# apple_all.net
KiCad netlist of a schematic drawn in EAGLE
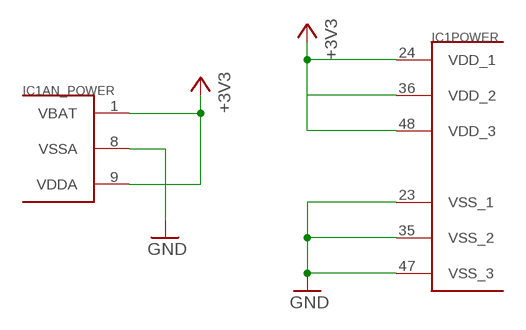
[diagram p0: schematic, sheet 1, part 1 of 2]
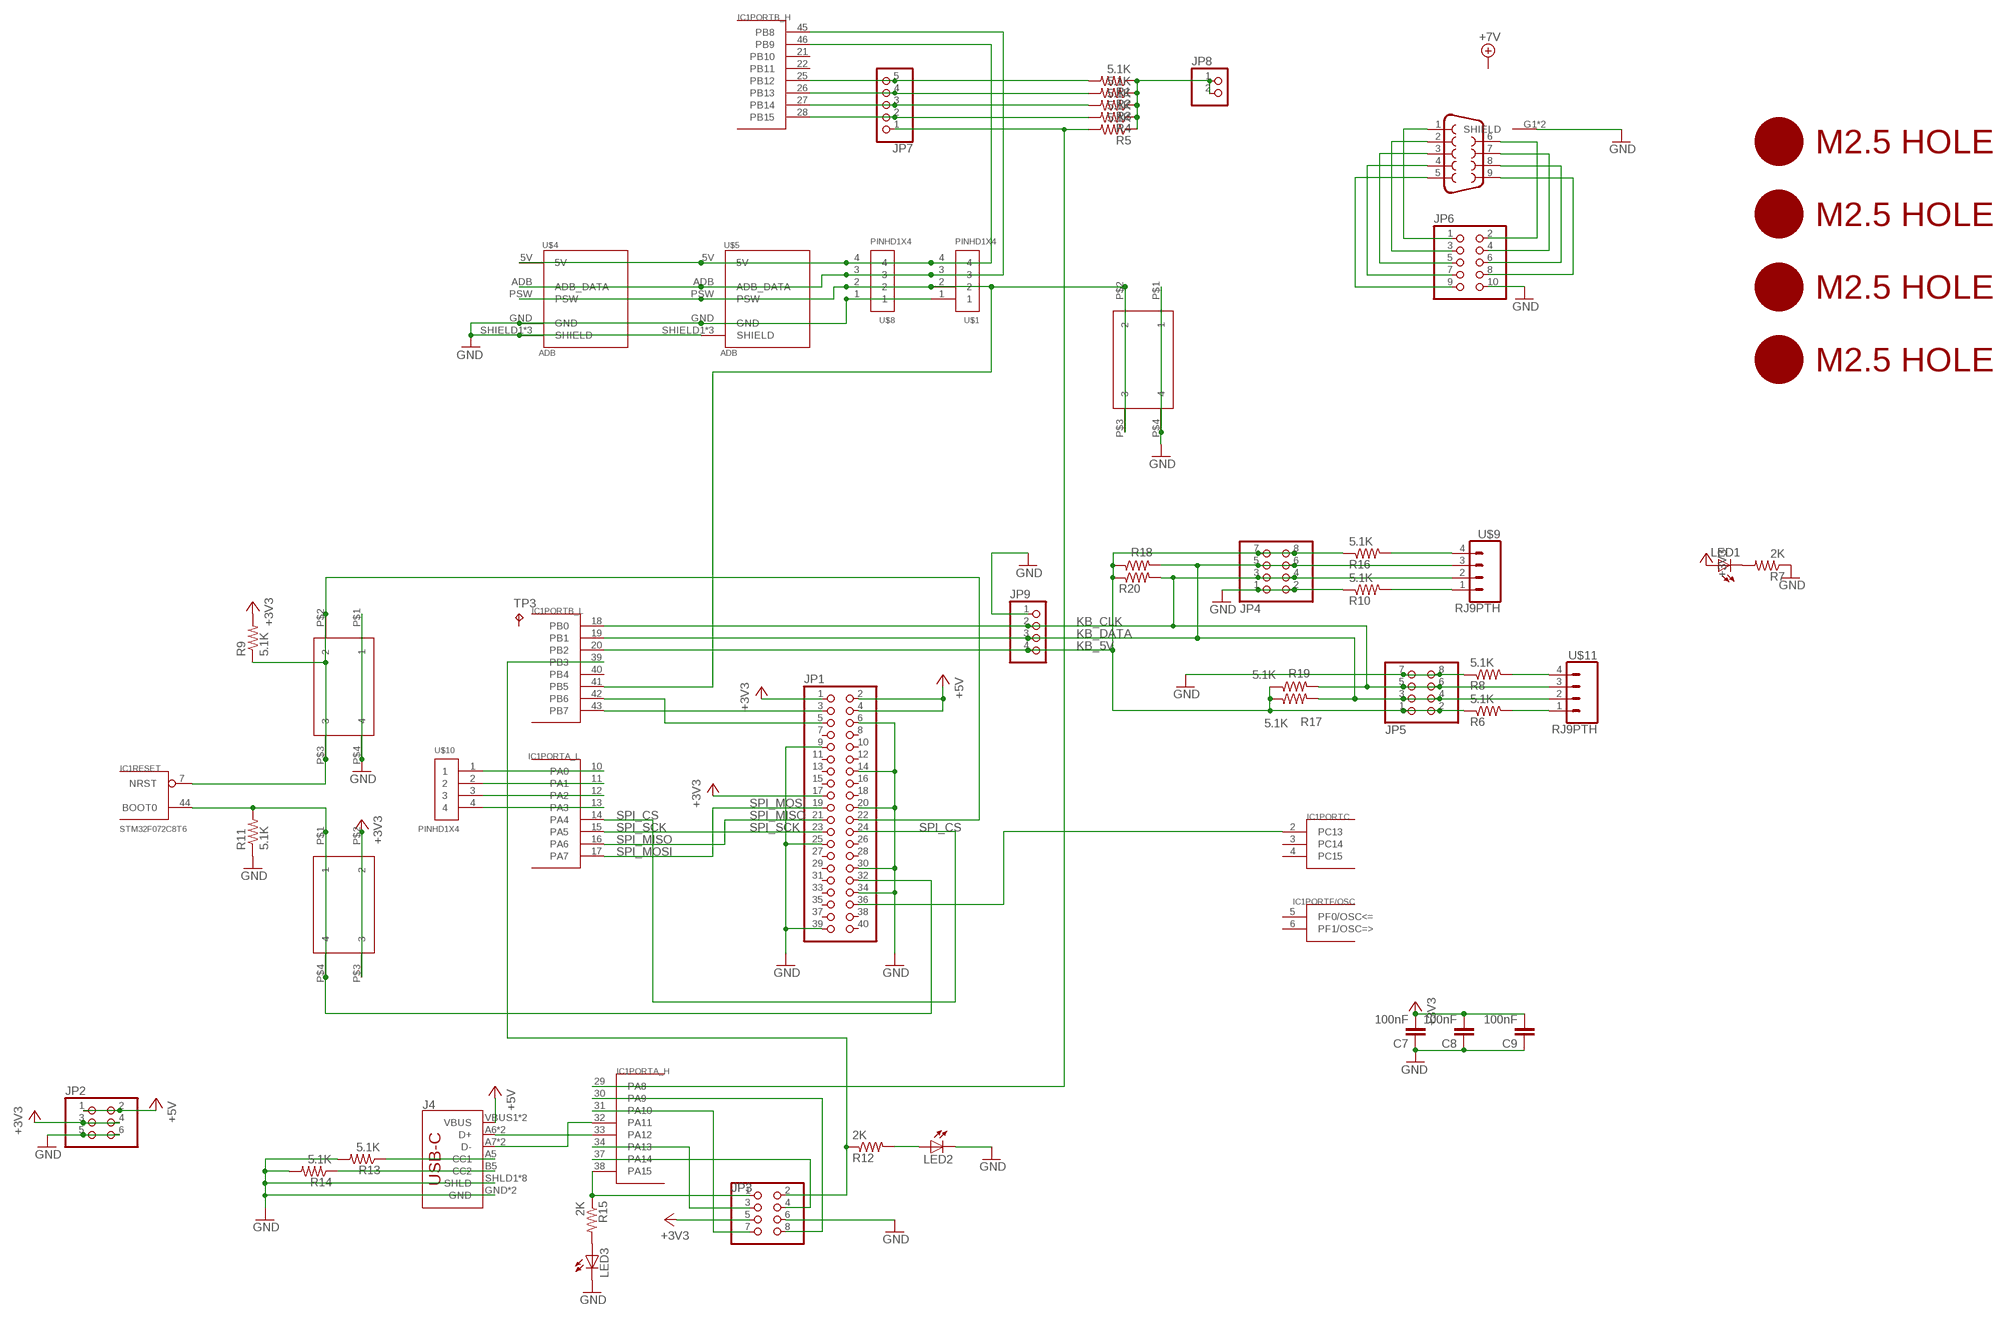
[diagram p1: schematic, sheet 1, part 2 of 2]

(export (version "E")
  (design (tool "Eeschema 10.0.6"))
  (components
    (comp (ref "C7")
      (value "100nF")
      (footprint "eagle-import:0805@1")
      (libsource (lib "eagle-import") (part "CAP0805"))
    )
    (comp (ref "C8")
      (value "100nF")
      (footprint "eagle-import:0805@1")
      (libsource (lib "eagle-import") (part "CAP0805"))
    )
    (comp (ref "C9")
      (value "100nF")
      (footprint "eagle-import:0805@1")
      (libsource (lib "eagle-import") (part "CAP0805"))
    )
    (comp (ref "IC1")
      (value "STM32F072C8T6")
      (footprint "eagle-import:TQFP48")
      (libsource (lib "eagle-import") (part "STM32F072C8T6"))
    )
    (comp (ref "J2")
      (value "DB9FEMALE")
      (footprint "eagle-import:DB9")
      (libsource (lib "eagle-import") (part "DB9FEMALE"))
    )
    (comp (ref "J4")
      (value "USB_C16PIN")
      (footprint "eagle-import:USB-C-16P")
      (libsource (lib "eagle-import") (part "USB_C16PIN"))
    )
    (comp (ref "JP1")
      (value "PINHD-2X20-BIG")
      (footprint "eagle-import:2X20-BIG")
      (libsource (lib "eagle-import") (part "PINHD-2X20-BIG"))
    )
    (comp (ref "JP2")
      (value "PINHD-2X3")
      (footprint "eagle-import:2X03")
      (libsource (lib "eagle-import") (part "PINHD-2X3"))
    )
    (comp (ref "JP3")
      (value "PINHD-2X4")
      (footprint "eagle-import:2X04")
      (libsource (lib "eagle-import") (part "PINHD-2X4"))
    )
    (comp (ref "JP4")
      (value "PINHD-2X4")
      (footprint "eagle-import:2X04")
      (libsource (lib "eagle-import") (part "PINHD-2X4"))
    )
    (comp (ref "JP5")
      (value "PINHD-2X4")
      (footprint "eagle-import:2X04")
      (libsource (lib "eagle-import") (part "PINHD-2X4"))
    )
    (comp (ref "JP6")
      (value "PINHD-2X5")
      (footprint "eagle-import:2X05")
      (libsource (lib "eagle-import") (part "PINHD-2X5"))
    )
    (comp (ref "JP7")
      (value "PINHD-1X5")
      (footprint "eagle-import:1X05")
      (libsource (lib "eagle-import") (part "PINHD-1X5"))
    )
    (comp (ref "JP8")
      (value "PINHD-1X2")
      (footprint "eagle-import:1X02")
      (libsource (lib "eagle-import") (part "PINHD-1X2"))
    )
    (comp (ref "JP9")
      (value "PINHD-1X4")
      (footprint "eagle-import:1X04")
      (libsource (lib "eagle-import") (part "PINHD-1X4"))
    )
    (comp (ref "LED1")
      (value "LEDCHIP-LED0805")
      (footprint "eagle-import:CHIP-LED0805")
      (libsource (lib "eagle-import") (part "LEDCHIP-LED0805"))
    )
    (comp (ref "LED2")
      (value "LEDCHIP-LED0805")
      (footprint "eagle-import:CHIP-LED0805")
      (libsource (lib "eagle-import") (part "LEDCHIP-LED0805"))
    )
    (comp (ref "LED3")
      (value "LEDCHIP-LED0805")
      (footprint "eagle-import:CHIP-LED0805")
      (libsource (lib "eagle-import") (part "LEDCHIP-LED0805"))
    )
    (comp (ref "R1")
      (value "5.1K")
      (footprint "eagle-import:0805")
      (libsource (lib "eagle-import") (part "RESISTOR0805-RES"))
    )
    (comp (ref "R2")
      (value "5.1K")
      (footprint "eagle-import:0805")
      (libsource (lib "eagle-import") (part "RESISTOR0805-RES"))
    )
    (comp (ref "R3")
      (value "5.1K")
      (footprint "eagle-import:0805")
      (libsource (lib "eagle-import") (part "RESISTOR0805-RES"))
    )
    (comp (ref "R4")
      (value "5.1K")
      (footprint "eagle-import:0805")
      (libsource (lib "eagle-import") (part "RESISTOR0805-RES"))
    )
    (comp (ref "R5")
      (value "5.1K")
      (footprint "eagle-import:0805")
      (libsource (lib "eagle-import") (part "RESISTOR0805-RES"))
    )
    (comp (ref "R6")
      (value "5.1K")
      (footprint "eagle-import:0805")
      (libsource (lib "eagle-import") (part "RESISTOR0805-RES"))
    )
    (comp (ref "R7")
      (value "2K")
      (footprint "eagle-import:0805")
      (libsource (lib "eagle-import") (part "RESISTOR0805-RES"))
    )
    (comp (ref "R8")
      (value "5.1K")
      (footprint "eagle-import:0805")
      (libsource (lib "eagle-import") (part "RESISTOR0805-RES"))
    )
    (comp (ref "R9")
      (value "5.1K")
      (footprint "eagle-import:0805")
      (libsource (lib "eagle-import") (part "RESISTOR0805-RES"))
    )
    (comp (ref "R10")
      (value "5.1K")
      (footprint "eagle-import:0805")
      (libsource (lib "eagle-import") (part "RESISTOR0805-RES"))
    )
    (comp (ref "R11")
      (value "5.1K")
      (footprint "eagle-import:0805")
      (libsource (lib "eagle-import") (part "RESISTOR0805-RES"))
    )
    (comp (ref "R12")
      (value "2K")
      (footprint "eagle-import:0805")
      (libsource (lib "eagle-import") (part "RESISTOR0805-RES"))
    )
    (comp (ref "R13")
      (value "5.1K")
      (footprint "eagle-import:0805")
      (libsource (lib "eagle-import") (part "RESISTOR0805-RES"))
    )
    (comp (ref "R14")
      (value "5.1K")
      (footprint "eagle-import:0805")
      (libsource (lib "eagle-import") (part "RESISTOR0805-RES"))
    )
    (comp (ref "R15")
      (value "2K")
      (footprint "eagle-import:0805")
      (libsource (lib "eagle-import") (part "RESISTOR0805-RES"))
    )
    (comp (ref "R16")
      (value "5.1K")
      (footprint "eagle-import:0805")
      (libsource (lib "eagle-import") (part "RESISTOR0805-RES"))
    )
    (comp (ref "R17")
      (value "5.1K")
      (footprint "eagle-import:0805")
      (libsource (lib "eagle-import") (part "RESISTOR0805-RES"))
    )
    (comp (ref "R18")
      (value "5.1K")
      (footprint "eagle-import:0805")
      (libsource (lib "eagle-import") (part "RESISTOR0805-RES"))
    )
    (comp (ref "R19")
      (value "5.1K")
      (footprint "eagle-import:0805")
      (libsource (lib "eagle-import") (part "RESISTOR0805-RES"))
    )
    (comp (ref "R20")
      (value "5.1K")
      (footprint "eagle-import:0805")
      (libsource (lib "eagle-import") (part "RESISTOR0805-RES"))
    )
    (comp (ref "SW1")
      (value "324_SW")
      (footprint "eagle-import:342_SWICH_FOOT")
      (libsource (lib "eagle-import") (part "324_SW"))
    )
    (comp (ref "SW2")
      (value "324_SW")
      (footprint "eagle-import:342_SWICH_FOOT")
      (libsource (lib "eagle-import") (part "324_SW"))
    )
    (comp (ref "SW3")
      (value "324_SW")
      (footprint "eagle-import:342_SWICH_FOOT")
      (libsource (lib "eagle-import") (part "324_SW"))
    )
    (comp (ref "TP3")
      (value "TPTP12R")
      (footprint "eagle-import:TP12R")
      (libsource (lib "eagle-import") (part "TPTP12R"))
    )
    (comp (ref "U$1")
      (value "PINHD1X4")
      (footprint "eagle-import:1X04-CLEANBIG")
      (libsource (lib "eagle-import") (part "PINHD1X4"))
    )
    (comp (ref "U$2")
      (value "M2.5HOLE")
      (footprint "eagle-import:M2.5HOLE")
      (libsource (lib "eagle-import") (part "M2.5HOLE"))
    )
    (comp (ref "U$3")
      (value "M2.5HOLE")
      (footprint "eagle-import:M2.5HOLE")
      (libsource (lib "eagle-import") (part "M2.5HOLE"))
    )
    (comp (ref "U$4")
      (value "ADB")
      (footprint "eagle-import:DIN4")
      (libsource (lib "eagle-import") (part "ADB"))
    )
    (comp (ref "U$5")
      (value "ADB")
      (footprint "eagle-import:DIN4")
      (libsource (lib "eagle-import") (part "ADB"))
    )
    (comp (ref "U$6")
      (value "M2.5HOLE")
      (footprint "eagle-import:M2.5HOLE")
      (libsource (lib "eagle-import") (part "M2.5HOLE"))
    )
    (comp (ref "U$7")
      (value "M2.5HOLE")
      (footprint "eagle-import:M2.5HOLE")
      (libsource (lib "eagle-import") (part "M2.5HOLE"))
    )
    (comp (ref "U$8")
      (value "PINHD1X4")
      (footprint "eagle-import:1X04-CLEANBIG")
      (libsource (lib "eagle-import") (part "PINHD1X4"))
    )
    (comp (ref "U$9")
      (value "RJ9PTH")
      (footprint "eagle-import:RJ9")
      (libsource (lib "eagle-import") (part "RJ9PTH"))
    )
    (comp (ref "U$10")
      (value "PINHD1X4")
      (footprint "eagle-import:1X04-CLEANBIG")
      (libsource (lib "eagle-import") (part "PINHD1X4"))
    )
    (comp (ref "U$11")
      (value "RJ9PTH")
      (footprint "eagle-import:RJ9")
      (libsource (lib "eagle-import") (part "RJ9PTH"))
    )
  )
  (nets
    (net (code "1") (name "+3V3") (class "Default")
      (node (ref "C7") (pin "2") (pinfunction "2_2") (pintype "passive"))
      (node (ref "C8") (pin "2") (pinfunction "2_2") (pintype "passive"))
      (node (ref "C9") (pin "2") (pinfunction "2_2") (pintype "passive"))
      (node (ref "IC1") (pin "1") (pinfunction "VBAT_1") (pintype "power_in"))
      (node (ref "IC1") (pin "24") (pinfunction "VDD_1_24") (pintype "power_in"))
      (node (ref "IC1") (pin "36") (pinfunction "VDD_2_36") (pintype "power_in"))
      (node (ref "IC1") (pin "48") (pinfunction "VDD_3_48") (pintype "power_in"))
      (node (ref "IC1") (pin "9") (pinfunction "VDDA_9") (pintype "power_in"))
      (node (ref "JP1") (pin "1") (pinfunction "1_1") (pintype "passive"))
      (node (ref "JP1") (pin "17") (pinfunction "17_17") (pintype "passive"))
      (node (ref "JP2") (pin "3") (pinfunction "3_3") (pintype "passive"))
      (node (ref "JP2") (pin "4") (pinfunction "4_4") (pintype "passive"))
      (node (ref "JP3") (pin "5") (pinfunction "5_5") (pintype "passive"))
      (node (ref "LED1") (pin "A") (pinfunction "A_A") (pintype "passive"))
      (node (ref "R9") (pin "2") (pinfunction "2_2") (pintype "passive"))
      (node (ref "SW2") (pin "P$2") (pinfunction "2_P$2") (pintype "bidirectional"))
      (node (ref "SW2") (pin "P$3") (pinfunction "3_P$3") (pintype "bidirectional"))
    )
    (net (code "2") (name "+5V") (class "Default")
      (node (ref "J4") (pin "VBUS1") (pinfunction "VBUS_VBUS1") (pintype "bidirectional"))
      (node (ref "J4") (pin "VBUS2") (pinfunction "VBUS_VBUS2") (pintype "bidirectional"))
      (node (ref "JP1") (pin "2") (pinfunction "2_2") (pintype "passive"))
      (node (ref "JP1") (pin "4") (pinfunction "4_4") (pintype "passive"))
      (node (ref "JP2") (pin "1") (pinfunction "1_1") (pintype "passive"))
      (node (ref "JP2") (pin "2") (pinfunction "2_2") (pintype "passive"))
    )
    (net (code "4") (name "/KB_5V") (class "Default")
      (node (ref "IC1") (pin "20") (pinfunction "PB2_20") (pintype "bidirectional"))
      (node (ref "JP4") (pin "7") (pinfunction "7_7") (pintype "passive"))
      (node (ref "JP4") (pin "8") (pinfunction "8_8") (pintype "passive"))
      (node (ref "JP5") (pin "1") (pinfunction "1_1") (pintype "passive"))
      (node (ref "JP5") (pin "2") (pinfunction "2_2") (pintype "passive"))
      (node (ref "JP9") (pin "4") (pinfunction "4_4") (pintype "passive"))
      (node (ref "R16") (pin "1") (pinfunction "1_1") (pintype "passive"))
      (node (ref "R17") (pin "1") (pinfunction "1_1") (pintype "passive"))
      (node (ref "R18") (pin "1") (pinfunction "1_1") (pintype "passive"))
      (node (ref "R19") (pin "1") (pinfunction "1_1") (pintype "passive"))
      (node (ref "R20") (pin "1") (pinfunction "1_1") (pintype "passive"))
      (node (ref "R6") (pin "1") (pinfunction "1_1") (pintype "passive"))
    )
    (net (code "5") (name "/KB_CLK") (class "Default")
      (node (ref "IC1") (pin "18") (pinfunction "PB0_18") (pintype "bidirectional"))
      (node (ref "JP4") (pin "3") (pinfunction "3_3") (pintype "passive"))
      (node (ref "JP4") (pin "4") (pinfunction "4_4") (pintype "passive"))
      (node (ref "JP5") (pin "5") (pinfunction "5_5") (pintype "passive"))
      (node (ref "JP5") (pin "6") (pinfunction "6_6") (pintype "passive"))
      (node (ref "JP9") (pin "2") (pinfunction "2_2") (pintype "passive"))
      (node (ref "R19") (pin "2") (pinfunction "2_2") (pintype "passive"))
      (node (ref "R20") (pin "2") (pinfunction "2_2") (pintype "passive"))
      (node (ref "U$11") (pin "3") (pinfunction "3_3") (pintype "passive"))
      (node (ref "U$9") (pin "2") (pinfunction "2_2") (pintype "passive"))
    )
    (net (code "6") (name "/KB_DATA") (class "Default")
      (node (ref "IC1") (pin "19") (pinfunction "PB1_19") (pintype "bidirectional"))
      (node (ref "JP4") (pin "5") (pinfunction "5_5") (pintype "passive"))
      (node (ref "JP4") (pin "6") (pinfunction "6_6") (pintype "passive"))
      (node (ref "JP5") (pin "3") (pinfunction "3_3") (pintype "passive"))
      (node (ref "JP5") (pin "4") (pinfunction "4_4") (pintype "passive"))
      (node (ref "JP9") (pin "3") (pinfunction "3_3") (pintype "passive"))
      (node (ref "R17") (pin "2") (pinfunction "2_2") (pintype "passive"))
      (node (ref "R18") (pin "2") (pinfunction "2_2") (pintype "passive"))
      (node (ref "U$11") (pin "2") (pinfunction "2_2") (pintype "passive"))
      (node (ref "U$9") (pin "3") (pinfunction "3_3") (pintype "passive"))
    )
    (net (code "7") (name "/SPI_CS") (class "Default")
      (node (ref "IC1") (pin "14") (pinfunction "PA4_14") (pintype "bidirectional"))
      (node (ref "JP1") (pin "24") (pinfunction "24_24") (pintype "passive"))
    )
    (net (code "8") (name "/SPI_MISO") (class "Default")
      (node (ref "IC1") (pin "16") (pinfunction "PA6_16") (pintype "bidirectional"))
      (node (ref "JP1") (pin "21") (pinfunction "21_21") (pintype "passive"))
    )
    (net (code "9") (name "/SPI_MOSI") (class "Default")
      (node (ref "IC1") (pin "17") (pinfunction "PA7_17") (pintype "bidirectional"))
      (node (ref "JP1") (pin "19") (pinfunction "19_19") (pintype "passive"))
    )
    (net (code "10") (name "/SPI_SCK") (class "Default")
      (node (ref "IC1") (pin "15") (pinfunction "PA5_15") (pintype "bidirectional"))
      (node (ref "JP1") (pin "23") (pinfunction "23_23") (pintype "passive"))
    )
    (net (code "11") (name "GND") (class "Default")
      (node (ref "C7") (pin "1") (pinfunction "1_1") (pintype "passive"))
      (node (ref "C8") (pin "1") (pinfunction "1_1") (pintype "passive"))
      (node (ref "C9") (pin "1") (pinfunction "1_1") (pintype "passive"))
      (node (ref "IC1") (pin "23") (pinfunction "VSS_1_23") (pintype "power_in"))
      (node (ref "IC1") (pin "35") (pinfunction "VSS_2_35") (pintype "power_in"))
      (node (ref "IC1") (pin "47") (pinfunction "VSS_3_47") (pintype "power_in"))
      (node (ref "IC1") (pin "8") (pinfunction "VSSA_8") (pintype "power_in"))
      (node (ref "J2") (pin "G1") (pinfunction "SHIELD_G1") (pintype "bidirectional"))
      (node (ref "J2") (pin "G2") (pinfunction "SHIELD_G2") (pintype "bidirectional"))
      (node (ref "J4") (pin "GND") (pinfunction "GND_GND") (pintype "bidirectional"))
      (node (ref "J4") (pin "GND2") (pinfunction "GND_GND2") (pintype "bidirectional"))
      (node (ref "J4") (pin "SHLD1") (pinfunction "SHLD_SHLD1") (pintype "bidirectional"))
      (node (ref "J4") (pin "SHLD2") (pinfunction "SHLD_SHLD2") (pintype "bidirectional"))
      (node (ref "J4") (pin "SHLD3") (pinfunction "SHLD_SHLD3") (pintype "bidirectional"))
      (node (ref "J4") (pin "SHLD4") (pinfunction "SHLD_SHLD4") (pintype "bidirectional"))
      (node (ref "J4") (pin "SHLD5") (pinfunction "SHLD_SHLD5") (pintype "bidirectional"))
      (node (ref "J4") (pin "SHLD6") (pinfunction "SHLD_SHLD6") (pintype "bidirectional"))
      (node (ref "J4") (pin "SHLD7") (pinfunction "SHLD_SHLD7") (pintype "bidirectional"))
      (node (ref "J4") (pin "SHLD8") (pinfunction "SHLD_SHLD8") (pintype "bidirectional"))
      (node (ref "JP1") (pin "14") (pinfunction "14_14") (pintype "passive"))
      (node (ref "JP1") (pin "20") (pinfunction "20_20") (pintype "passive"))
      (node (ref "JP1") (pin "25") (pinfunction "25_25") (pintype "passive"))
      (node (ref "JP1") (pin "30") (pinfunction "30_30") (pintype "passive"))
      (node (ref "JP1") (pin "34") (pinfunction "34_34") (pintype "passive"))
      (node (ref "JP1") (pin "39") (pinfunction "39_39") (pintype "passive"))
      (node (ref "JP1") (pin "6") (pinfunction "6_6") (pintype "passive"))
      (node (ref "JP1") (pin "9") (pinfunction "9_9") (pintype "passive"))
      (node (ref "JP2") (pin "5") (pinfunction "5_5") (pintype "passive"))
      (node (ref "JP2") (pin "6") (pinfunction "6_6") (pintype "passive"))
      (node (ref "JP3") (pin "6") (pinfunction "6_6") (pintype "passive"))
      (node (ref "JP4") (pin "1") (pinfunction "1_1") (pintype "passive"))
      (node (ref "JP4") (pin "2") (pinfunction "2_2") (pintype "passive"))
      (node (ref "JP5") (pin "7") (pinfunction "7_7") (pintype "passive"))
      (node (ref "JP5") (pin "8") (pinfunction "8_8") (pintype "passive"))
      (node (ref "JP6") (pin "10") (pinfunction "10_10") (pintype "passive"))
      (node (ref "JP9") (pin "1") (pinfunction "1_1") (pintype "passive"))
      (node (ref "LED2") (pin "C") (pinfunction "C_C") (pintype "passive"))
      (node (ref "LED3") (pin "C") (pinfunction "C_C") (pintype "passive"))
      (node (ref "R10") (pin "1") (pinfunction "1_1") (pintype "passive"))
      (node (ref "R11") (pin "1") (pinfunction "1_1") (pintype "passive"))
      (node (ref "R13") (pin "2") (pinfunction "2_2") (pintype "passive"))
      (node (ref "R14") (pin "2") (pinfunction "2_2") (pintype "passive"))
      (node (ref "R7") (pin "1") (pinfunction "1_1") (pintype "passive"))
      (node (ref "R8") (pin "1") (pinfunction "1_1") (pintype "passive"))
      (node (ref "SW1") (pin "P$1") (pinfunction "1_P$1") (pintype "bidirectional"))
      (node (ref "SW1") (pin "P$4") (pinfunction "4_P$4") (pintype "bidirectional"))
      (node (ref "SW3") (pin "P$1") (pinfunction "1_P$1") (pintype "bidirectional"))
      (node (ref "SW3") (pin "P$4") (pinfunction "4_P$4") (pintype "bidirectional"))
      (node (ref "U$1") (pin "1") (pinfunction "1_1") (pintype "bidirectional"))
      (node (ref "U$4") (pin "GND") (pinfunction "GND_GND") (pintype "bidirectional"))
      (node (ref "U$4") (pin "SHIELD1") (pinfunction "SHIELD_SHIELD1") (pintype "bidirectional"))
      (node (ref "U$4") (pin "SHIELD2") (pinfunction "SHIELD_SHIELD2") (pintype "bidirectional"))
      (node (ref "U$4") (pin "SHIELD3") (pinfunction "SHIELD_SHIELD3") (pintype "bidirectional"))
      (node (ref "U$5") (pin "GND") (pinfunction "GND_GND") (pintype "bidirectional"))
      (node (ref "U$5") (pin "SHIELD1") (pinfunction "SHIELD_SHIELD1") (pintype "bidirectional"))
      (node (ref "U$5") (pin "SHIELD2") (pinfunction "SHIELD_SHIELD2") (pintype "bidirectional"))
      (node (ref "U$5") (pin "SHIELD3") (pinfunction "SHIELD_SHIELD3") (pintype "bidirectional"))
      (node (ref "U$8") (pin "1") (pinfunction "1_1") (pintype "bidirectional"))
    )
    (net (code "12") (name "Net-(IC1B-PA8)") (class "Default")
      (node (ref "IC1") (pin "29") (pinfunction "PA8_29") (pintype "bidirectional"))
      (node (ref "JP7") (pin "1") (pinfunction "1_1") (pintype "passive"))
      (node (ref "R5") (pin "2") (pinfunction "2_2") (pintype "passive"))
    )
    (net (code "13") (name "Net-(IC1B-PA9)") (class "Default")
      (node (ref "IC1") (pin "30") (pinfunction "PA9_30") (pintype "bidirectional"))
      (node (ref "JP3") (pin "8") (pinfunction "8_8") (pintype "passive"))
    )
    (net (code "14") (name "Net-(IC1B-PA10)") (class "Default")
      (node (ref "IC1") (pin "31") (pinfunction "PA10_31") (pintype "bidirectional"))
      (node (ref "JP3") (pin "7") (pinfunction "7_7") (pintype "passive"))
    )
    (net (code "15") (name "Net-(IC1B-PA11)") (class "Default")
      (node (ref "IC1") (pin "32") (pinfunction "PA11_32") (pintype "bidirectional"))
      (node (ref "J4") (pin "A7") (pinfunction "D-_A7") (pintype "bidirectional"))
      (node (ref "J4") (pin "B7") (pinfunction "D-_B7") (pintype "bidirectional"))
    )
    (net (code "16") (name "Net-(IC1B-PA12)") (class "Default")
      (node (ref "IC1") (pin "33") (pinfunction "PA12_33") (pintype "bidirectional"))
      (node (ref "J4") (pin "A6") (pinfunction "D+_A6") (pintype "bidirectional"))
      (node (ref "J4") (pin "B6") (pinfunction "D+_B6") (pintype "bidirectional"))
    )
    (net (code "17") (name "Net-(IC1B-PA13)") (class "Default")
      (node (ref "IC1") (pin "34") (pinfunction "PA13_34") (pintype "bidirectional"))
      (node (ref "JP3") (pin "3") (pinfunction "3_3") (pintype "passive"))
    )
    (net (code "18") (name "Net-(IC1B-PA14)") (class "Default")
      (node (ref "IC1") (pin "37") (pinfunction "PA14_37") (pintype "bidirectional"))
      (node (ref "JP3") (pin "4") (pinfunction "4_4") (pintype "passive"))
    )
    (net (code "19") (name "Net-(IC1B-PA15)") (class "Default")
      (node (ref "IC1") (pin "38") (pinfunction "PA15_38") (pintype "bidirectional"))
      (node (ref "JP3") (pin "1") (pinfunction "1_1") (pintype "passive"))
      (node (ref "R15") (pin "1") (pinfunction "1_1") (pintype "passive"))
    )
    (net (code "20") (name "Net-(IC1C-PA0)") (class "Default")
      (node (ref "IC1") (pin "10") (pinfunction "PA0_10") (pintype "bidirectional"))
      (node (ref "U$10") (pin "1") (pinfunction "1_1") (pintype "bidirectional"))
    )
    (net (code "21") (name "Net-(IC1C-PA1)") (class "Default")
      (node (ref "IC1") (pin "11") (pinfunction "PA1_11") (pintype "bidirectional"))
      (node (ref "U$10") (pin "2") (pinfunction "2_2") (pintype "bidirectional"))
    )
    (net (code "22") (name "Net-(IC1C-PA2)") (class "Default")
      (node (ref "IC1") (pin "12") (pinfunction "PA2_12") (pintype "bidirectional"))
      (node (ref "U$10") (pin "3") (pinfunction "3_3") (pintype "bidirectional"))
    )
    (net (code "23") (name "Net-(IC1C-PA3)") (class "Default")
      (node (ref "IC1") (pin "13") (pinfunction "PA3_13") (pintype "bidirectional"))
      (node (ref "U$10") (pin "4") (pinfunction "4_4") (pintype "bidirectional"))
    )
    (net (code "24") (name "Net-(IC1D-PB8)") (class "Default")
      (node (ref "IC1") (pin "45") (pinfunction "PB8_45") (pintype "bidirectional"))
      (node (ref "U$1") (pin "3") (pinfunction "3_3") (pintype "bidirectional"))
      (node (ref "U$4") (pin "ADB") (pinfunction "ADB_DATA_ADB") (pintype "bidirectional"))
      (node (ref "U$5") (pin "ADB") (pinfunction "ADB_DATA_ADB") (pintype "bidirectional"))
      (node (ref "U$8") (pin "3") (pinfunction "3_3") (pintype "bidirectional"))
    )
    (net (code "25") (name "Net-(IC1D-PB9)") (class "Default")
      (node (ref "IC1") (pin "46") (pinfunction "PB9_46") (pintype "bidirectional"))
      (node (ref "U$1") (pin "4") (pinfunction "4_4") (pintype "bidirectional"))
      (node (ref "U$4") (pin "5V") (pinfunction "5V_5V") (pintype "bidirectional"))
      (node (ref "U$5") (pin "5V") (pinfunction "5V_5V") (pintype "bidirectional"))
      (node (ref "U$8") (pin "4") (pinfunction "4_4") (pintype "bidirectional"))
    )
    (net (code "26") (name "Net-(IC1D-PB12)") (class "Default")
      (node (ref "IC1") (pin "25") (pinfunction "PB12_25") (pintype "bidirectional"))
      (node (ref "JP7") (pin "5") (pinfunction "5_5") (pintype "passive"))
      (node (ref "R1") (pin "2") (pinfunction "2_2") (pintype "passive"))
    )
    (net (code "27") (name "Net-(IC1D-PB13)") (class "Default")
      (node (ref "IC1") (pin "26") (pinfunction "PB13_26") (pintype "bidirectional"))
      (node (ref "JP7") (pin "4") (pinfunction "4_4") (pintype "passive"))
      (node (ref "R2") (pin "2") (pinfunction "2_2") (pintype "passive"))
    )
    (net (code "28") (name "Net-(IC1D-PB14)") (class "Default")
      (node (ref "IC1") (pin "27") (pinfunction "PB14_27") (pintype "bidirectional"))
      (node (ref "JP7") (pin "3") (pinfunction "3_3") (pintype "passive"))
      (node (ref "R3") (pin "2") (pinfunction "2_2") (pintype "passive"))
    )
    (net (code "29") (name "Net-(IC1D-PB15)") (class "Default")
      (node (ref "IC1") (pin "28") (pinfunction "PB15_28") (pintype "bidirectional"))
      (node (ref "JP7") (pin "2") (pinfunction "2_2") (pintype "passive"))
      (node (ref "R4") (pin "2") (pinfunction "2_2") (pintype "passive"))
    )
    (net (code "30") (name "Net-(IC1E-PB3)") (class "Default")
      (node (ref "IC1") (pin "39") (pinfunction "PB3_39") (pintype "bidirectional"))
      (node (ref "JP3") (pin "2") (pinfunction "2_2") (pintype "passive"))
      (node (ref "R12") (pin "1") (pinfunction "1_1") (pintype "passive"))
    )
    (net (code "31") (name "Net-(IC1E-PB5)") (class "Default")
      (node (ref "IC1") (pin "41") (pinfunction "PB5_41") (pintype "bidirectional"))
      (node (ref "SW3") (pin "P$2") (pinfunction "2_P$2") (pintype "bidirectional"))
      (node (ref "SW3") (pin "P$3") (pinfunction "3_P$3") (pintype "bidirectional"))
      (node (ref "U$1") (pin "2") (pinfunction "2_2") (pintype "bidirectional"))
      (node (ref "U$4") (pin "PSW") (pinfunction "PSW_PSW") (pintype "bidirectional"))
      (node (ref "U$5") (pin "PSW") (pinfunction "PSW_PSW") (pintype "bidirectional"))
      (node (ref "U$8") (pin "2") (pinfunction "2_2") (pintype "bidirectional"))
    )
    (net (code "32") (name "Net-(IC1E-PB6)") (class "Default")
      (node (ref "IC1") (pin "42") (pinfunction "PB6_42") (pintype "bidirectional"))
      (node (ref "JP1") (pin "5") (pinfunction "5_5") (pintype "passive"))
    )
    (net (code "33") (name "Net-(IC1E-PB7)") (class "Default")
      (node (ref "IC1") (pin "43") (pinfunction "PB7_43") (pintype "bidirectional"))
      (node (ref "JP1") (pin "3") (pinfunction "3_3") (pintype "passive"))
    )
    (net (code "34") (name "Net-(IC1F-PC13)") (class "Default")
      (node (ref "IC1") (pin "2") (pinfunction "PC13_2") (pintype "bidirectional"))
      (node (ref "JP1") (pin "36") (pinfunction "36_36") (pintype "passive"))
    )
    (net (code "35") (name "Net-(IC1I-BOOT0)") (class "Default")
      (node (ref "IC1") (pin "44") (pinfunction "BOOT0_44") (pintype "input"))
      (node (ref "JP1") (pin "32") (pinfunction "32_32") (pintype "passive"))
      (node (ref "R11") (pin "2") (pinfunction "2_2") (pintype "passive"))
      (node (ref "SW2") (pin "P$1") (pinfunction "1_P$1") (pintype "bidirectional"))
      (node (ref "SW2") (pin "P$4") (pinfunction "4_P$4") (pintype "bidirectional"))
    )
    (net (code "36") (name "Net-(IC1I-NRST)") (class "Default")
      (node (ref "IC1") (pin "7") (pinfunction "NRST_7") (pintype "input"))
      (node (ref "JP1") (pin "22") (pinfunction "22_22") (pintype "passive"))
      (node (ref "R9") (pin "1") (pinfunction "1_1") (pintype "passive"))
      (node (ref "SW1") (pin "P$2") (pinfunction "2_P$2") (pintype "bidirectional"))
      (node (ref "SW1") (pin "P$3") (pinfunction "3_P$3") (pintype "bidirectional"))
    )
    (net (code "37") (name "Net-(J2-Pad1)") (class "Default")
      (node (ref "J2") (pin "1") (pinfunction "1_1") (pintype "passive"))
      (node (ref "JP6") (pin "1") (pinfunction "1_1") (pintype "passive"))
    )
    (net (code "38") (name "Net-(J2-Pad2)") (class "Default")
      (node (ref "J2") (pin "2") (pinfunction "2_2") (pintype "passive"))
      (node (ref "JP6") (pin "3") (pinfunction "3_3") (pintype "passive"))
    )
    (net (code "39") (name "Net-(J2-Pad3)") (class "Default")
      (node (ref "J2") (pin "3") (pinfunction "3_3") (pintype "passive"))
      (node (ref "JP6") (pin "5") (pinfunction "5_5") (pintype "passive"))
    )
    (net (code "40") (name "Net-(J2-Pad4)") (class "Default")
      (node (ref "J2") (pin "4") (pinfunction "4_4") (pintype "passive"))
      (node (ref "JP6") (pin "7") (pinfunction "7_7") (pintype "passive"))
    )
    (net (code "41") (name "Net-(J2-Pad5)") (class "Default")
      (node (ref "J2") (pin "5") (pinfunction "5_5") (pintype "passive"))
      (node (ref "JP6") (pin "9") (pinfunction "9_9") (pintype "passive"))
    )
    (net (code "42") (name "Net-(J2-Pad6)") (class "Default")
      (node (ref "J2") (pin "6") (pinfunction "6_6") (pintype "passive"))
      (node (ref "JP6") (pin "2") (pinfunction "2_2") (pintype "passive"))
    )
    (net (code "43") (name "Net-(J2-Pad7)") (class "Default")
      (node (ref "J2") (pin "7") (pinfunction "7_7") (pintype "passive"))
      (node (ref "JP6") (pin "4") (pinfunction "4_4") (pintype "passive"))
    )
    (net (code "44") (name "Net-(J2-Pad8)") (class "Default")
      (node (ref "J2") (pin "8") (pinfunction "8_8") (pintype "passive"))
      (node (ref "JP6") (pin "6") (pinfunction "6_6") (pintype "passive"))
    )
    (net (code "45") (name "Net-(J2-Pad9)") (class "Default")
      (node (ref "J2") (pin "9") (pinfunction "9_9") (pintype "passive"))
      (node (ref "JP6") (pin "8") (pinfunction "8_8") (pintype "passive"))
    )
    (net (code "46") (name "Net-(J4-CC1)") (class "Default")
      (node (ref "J4") (pin "A5") (pinfunction "CC1_A5") (pintype "bidirectional"))
      (node (ref "R13") (pin "1") (pinfunction "1_1") (pintype "passive"))
    )
    (net (code "47") (name "Net-(J4-CC2)") (class "Default")
      (node (ref "J4") (pin "B5") (pinfunction "CC2_B5") (pintype "bidirectional"))
      (node (ref "R14") (pin "1") (pinfunction "1_1") (pintype "passive"))
    )
    (net (code "48") (name "Net-(JP8-Pad1)") (class "Default")
      (node (ref "JP8") (pin "1") (pinfunction "1_1") (pintype "passive"))
      (node (ref "JP8") (pin "2") (pinfunction "2_2") (pintype "passive"))
      (node (ref "R1") (pin "1") (pinfunction "1_1") (pintype "passive"))
      (node (ref "R2") (pin "1") (pinfunction "1_1") (pintype "passive"))
      (node (ref "R3") (pin "1") (pinfunction "1_1") (pintype "passive"))
      (node (ref "R4") (pin "1") (pinfunction "1_1") (pintype "passive"))
      (node (ref "R5") (pin "1") (pinfunction "1_1") (pintype "passive"))
    )
    (net (code "49") (name "Net-(LED1-PadC)") (class "Default")
      (node (ref "LED1") (pin "C") (pinfunction "C_C") (pintype "passive"))
      (node (ref "R7") (pin "2") (pinfunction "2_2") (pintype "passive"))
    )
    (net (code "50") (name "Net-(LED2-PadA)") (class "Default")
      (node (ref "LED2") (pin "A") (pinfunction "A_A") (pintype "passive"))
      (node (ref "R12") (pin "2") (pinfunction "2_2") (pintype "passive"))
    )
    (net (code "51") (name "Net-(LED3-PadA)") (class "Default")
      (node (ref "LED3") (pin "A") (pinfunction "A_A") (pintype "passive"))
      (node (ref "R15") (pin "2") (pinfunction "2_2") (pintype "passive"))
    )
    (net (code "52") (name "Net-(R6-Pad2)") (class "Default")
      (node (ref "R6") (pin "2") (pinfunction "2_2") (pintype "passive"))
      (node (ref "U$11") (pin "1") (pinfunction "1_1") (pintype "passive"))
    )
    (net (code "53") (name "Net-(R8-Pad2)") (class "Default")
      (node (ref "R8") (pin "2") (pinfunction "2_2") (pintype "passive"))
      (node (ref "U$11") (pin "4") (pinfunction "4_4") (pintype "passive"))
    )
    (net (code "54") (name "Net-(R10-Pad2)") (class "Default")
      (node (ref "R10") (pin "2") (pinfunction "2_2") (pintype "passive"))
      (node (ref "U$9") (pin "1") (pinfunction "1_1") (pintype "passive"))
    )
    (net (code "55") (name "Net-(R16-Pad2)") (class "Default")
      (node (ref "R16") (pin "2") (pinfunction "2_2") (pintype "passive"))
      (node (ref "U$9") (pin "4") (pinfunction "4_4") (pintype "passive"))
    )
    (net (code "56") (name "unconnected-(IC1D-PB10-Pad21)") (class "Default")
      (node (ref "IC1") (pin "21") (pinfunction "PB10_21") (pintype "bidirectional"))
    )
    (net (code "57") (name "unconnected-(IC1D-PB11-Pad22)") (class "Default")
      (node (ref "IC1") (pin "22") (pinfunction "PB11_22") (pintype "bidirectional"))
    )
    (net (code "58") (name "unconnected-(IC1E-PB4-Pad40)") (class "Default")
      (node (ref "IC1") (pin "40") (pinfunction "PB4_40") (pintype "bidirectional"))
    )
    (net (code "59") (name "unconnected-(IC1F-PC14-Pad3)") (class "Default")
      (node (ref "IC1") (pin "3") (pinfunction "PC14_3") (pintype "bidirectional"))
    )
    (net (code "60") (name "unconnected-(IC1F-PC15-Pad4)") (class "Default")
      (node (ref "IC1") (pin "4") (pinfunction "PC15_4") (pintype "bidirectional"))
    )
    (net (code "61") (name "unconnected-(IC1G-PF0{slash}OSC<=-Pad5)") (class "Default")
      (node (ref "IC1") (pin "5") (pinfunction "PF0/OSC<=_5") (pintype "bidirectional"))
    )
    (net (code "62") (name "unconnected-(IC1G-PF1{slash}OSC=>-Pad6)") (class "Default")
      (node (ref "IC1") (pin "6") (pinfunction "PF1/OSC=>_6") (pintype "bidirectional"))
    )
    (net (code "63") (name "unconnected-(JP1-Pad7)") (class "Default")
      (node (ref "JP1") (pin "7") (pinfunction "7_7") (pintype "passive"))
    )
    (net (code "64") (name "unconnected-(JP1-Pad8)") (class "Default")
      (node (ref "JP1") (pin "8") (pinfunction "8_8") (pintype "passive"))
    )
    (net (code "65") (name "unconnected-(JP1-Pad10)") (class "Default")
      (node (ref "JP1") (pin "10") (pinfunction "10_10") (pintype "passive"))
    )
    (net (code "66") (name "unconnected-(JP1-Pad11)") (class "Default")
      (node (ref "JP1") (pin "11") (pinfunction "11_11") (pintype "passive"))
    )
    (net (code "67") (name "unconnected-(JP1-Pad12)") (class "Default")
      (node (ref "JP1") (pin "12") (pinfunction "12_12") (pintype "passive"))
    )
    (net (code "68") (name "unconnected-(JP1-Pad13)") (class "Default")
      (node (ref "JP1") (pin "13") (pinfunction "13_13") (pintype "passive"))
    )
    (net (code "69") (name "unconnected-(JP1-Pad15)") (class "Default")
      (node (ref "JP1") (pin "15") (pinfunction "15_15") (pintype "passive"))
    )
    (net (code "70") (name "unconnected-(JP1-Pad16)") (class "Default")
      (node (ref "JP1") (pin "16") (pinfunction "16_16") (pintype "passive"))
    )
    (net (code "71") (name "unconnected-(JP1-Pad18)") (class "Default")
      (node (ref "JP1") (pin "18") (pinfunction "18_18") (pintype "passive"))
    )
    (net (code "72") (name "unconnected-(JP1-Pad26)") (class "Default")
      (node (ref "JP1") (pin "26") (pinfunction "26_26") (pintype "passive"))
    )
    (net (code "73") (name "unconnected-(JP1-Pad27)") (class "Default")
      (node (ref "JP1") (pin "27") (pinfunction "27_27") (pintype "passive"))
    )
    (net (code "74") (name "unconnected-(JP1-Pad28)") (class "Default")
      (node (ref "JP1") (pin "28") (pinfunction "28_28") (pintype "passive"))
    )
    (net (code "75") (name "unconnected-(JP1-Pad29)") (class "Default")
      (node (ref "JP1") (pin "29") (pinfunction "29_29") (pintype "passive"))
    )
    (net (code "76") (name "unconnected-(JP1-Pad31)") (class "Default")
      (node (ref "JP1") (pin "31") (pinfunction "31_31") (pintype "passive"))
    )
    (net (code "77") (name "unconnected-(JP1-Pad33)") (class "Default")
      (node (ref "JP1") (pin "33") (pinfunction "33_33") (pintype "passive"))
    )
    (net (code "78") (name "unconnected-(JP1-Pad35)") (class "Default")
      (node (ref "JP1") (pin "35") (pinfunction "35_35") (pintype "passive"))
    )
    (net (code "79") (name "unconnected-(JP1-Pad37)") (class "Default")
      (node (ref "JP1") (pin "37") (pinfunction "37_37") (pintype "passive"))
    )
    (net (code "80") (name "unconnected-(JP1-Pad38)") (class "Default")
      (node (ref "JP1") (pin "38") (pinfunction "38_38") (pintype "passive"))
    )
    (net (code "81") (name "unconnected-(JP1-Pad40)") (class "Default")
      (node (ref "JP1") (pin "40") (pinfunction "40_40") (pintype "passive"))
    )
    (net (code "82") (name "unconnected-(TP3-PadTP)") (class "Default")
      (node (ref "TP3") (pin "TP") (pinfunction "TP_TP") (pintype "input"))
    )
  )
)
